# motor_controller.net
KiCad netlist of a schematic drawn in Altium Designer
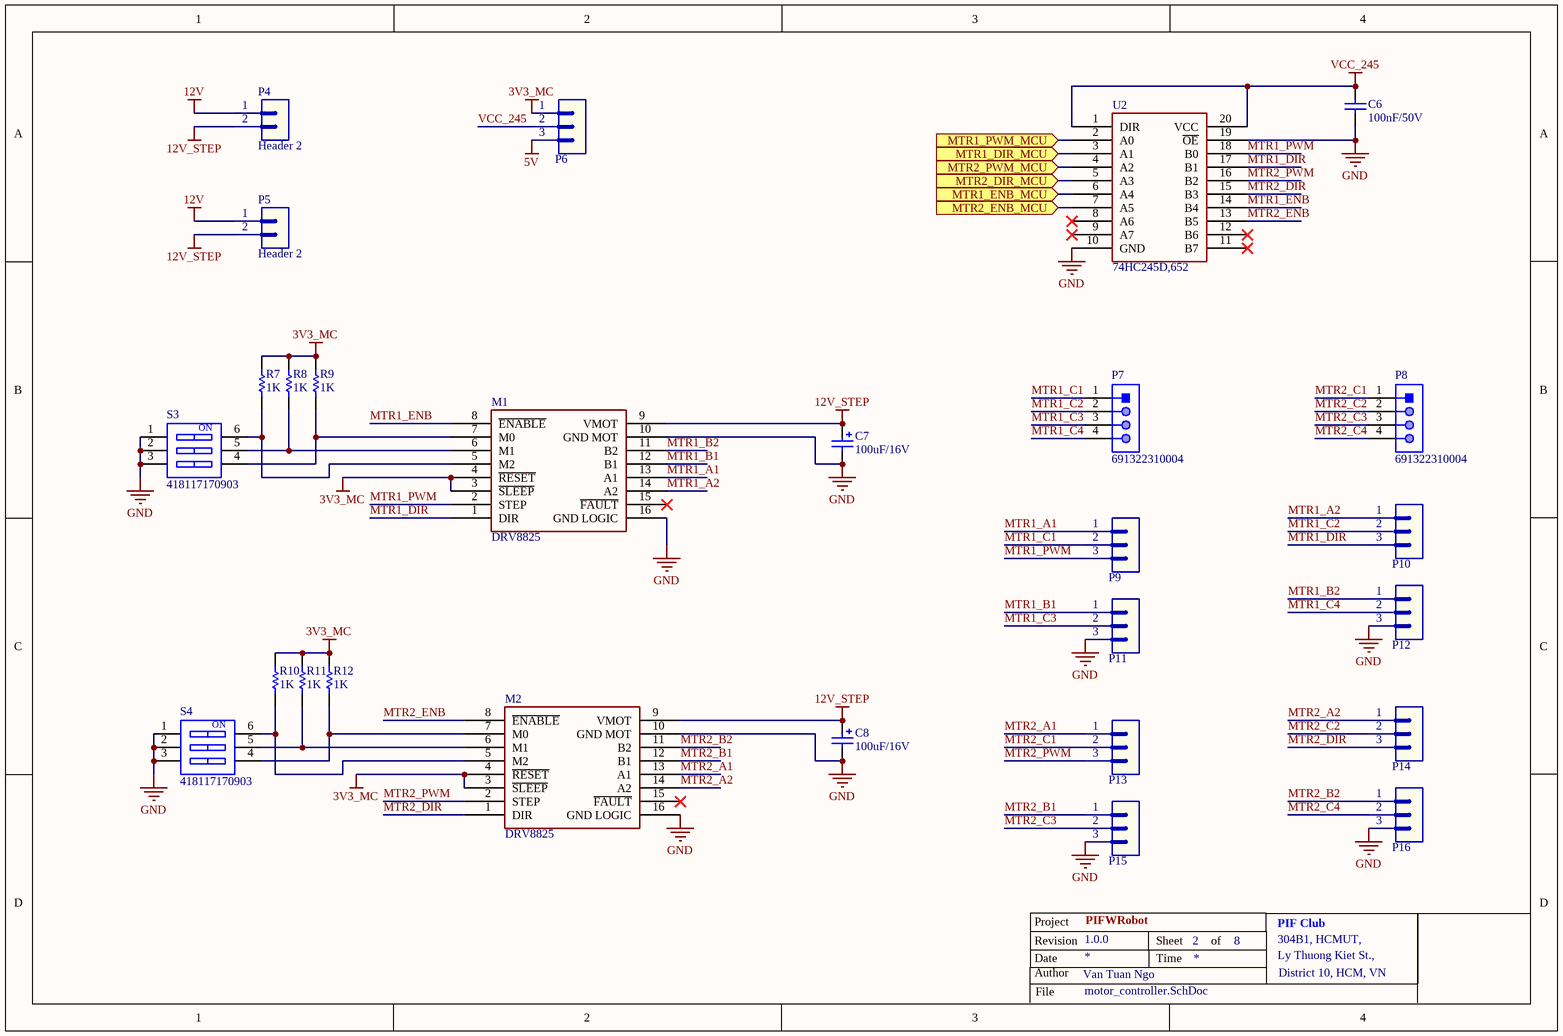
[diagram p0: motor_controller.SchDoc]

(export (version "E")
  (design (tool "Eeschema 10.0.6"))
  (components
    (comp (ref "C6")
      (value "100nF/50V")
      (footprint "CAP-SM-0805")
      (description "CAP CER 0.1UF 50V Y5V 0805")
      (fields
        (field (name "MANUFACTURER") "Samsung Electro-Mechanics")
        (field (name "MANUFACTURER PART NUMBER") "CL21F104ZBCNNNC")
      )
      (libsource (lib "Capacitor") (part "Cap-100nF-50V-0805"))
    )
    (comp (ref "C7")
      (value "100uF/16V")
      (footprint "CAP-SM-AL-SIZE-D-D6L6")
      (description "CAP ALUM 100UF 20% 16V SMD")
      (fields
        (field (name "MANUFACTURER") "Nichicon")
        (field (name "MANUFACTURER PART NUMBER") "UWX1C101MCL1GB")
      )
      (libsource (lib "Capacitor") (part "Cap-Al-100uF-16V-D6L5"))
    )
    (comp (ref "C8")
      (value "100uF/16V")
      (footprint "CAP-SM-AL-SIZE-D-D6L6")
      (description "CAP ALUM 100UF 20% 16V SMD")
      (fields
        (field (name "MANUFACTURER") "Nichicon")
        (field (name "MANUFACTURER PART NUMBER") "UWX1C101MCL1GB")
      )
      (libsource (lib "Capacitor") (part "Cap-Al-100uF-16V-D6L5"))
    )
    (comp (ref "M1") (value "DRV8825") (footprint "DRV8825") (libsource (lib "PIFWRobot") (part "DRV8825")))
    (comp (ref "M2") (value "DRV8825") (footprint "DRV8825") (libsource (lib "PIFWRobot") (part "DRV8825")))
    (comp (ref "P4")
      (value "Header 2")
      (footprint "JP2")
      (description "Header, 2-Pin")
      (fields (field (name "LOCAL SUPPLIER PART NUMBER") "x") (field (name "PUBLISHER") "Altium Limited"))
      (libsource (lib "Header-Connector") (part "Header 2"))
    )
    (comp (ref "P5")
      (value "Header 2")
      (footprint "JP2")
      (description "Header, 2-Pin")
      (fields (field (name "LOCAL SUPPLIER PART NUMBER") "x") (field (name "PUBLISHER") "Altium Limited"))
      (libsource (lib "Header-Connector") (part "Header 2"))
    )
    (comp (ref "P6")
      (value "Header 3")
      (footprint "JP3")
      (description "Header, 3-Pin")
      (fields (field (name "LOCAL SUPPLIER PART NUMBER") "x") (field (name "PUBLISHER") "Altium Limited"))
      (libsource (lib "Header-Connector") (part "Header 3"))
    )
    (comp (ref "P7")
      (value "691322310004")
      (footprint "691322310004")
      (description "WR-TBL Serie 322 Horizontal PCB Header, Pluggable, pitch 3.81mm, 4p")
      (fields (field (name "LOCAL SUPLIER PART NUMBER") "x") (field (name "PUBLISHER") "Wurth Elektronik"))
      (libsource (lib "terminal_block") (part "691322310004"))
    )
    (comp (ref "P8")
      (value "691322310004")
      (footprint "691322310004")
      (description "WR-TBL Serie 322 Horizontal PCB Header, Pluggable, pitch 3.81mm, 4p")
      (fields (field (name "LOCAL SUPLIER PART NUMBER") "x") (field (name "PUBLISHER") "Wurth Elektronik"))
      (libsource (lib "terminal_block") (part "691322310004"))
    )
    (comp (ref "P9")
      (value "Header 3")
      (footprint "JP3")
      (description "Header, 3-Pin")
      (fields (field (name "LOCAL SUPPLIER PART NUMBER") "x") (field (name "PUBLISHER") "Altium Limited"))
      (libsource (lib "Header-Connector") (part "Header 3"))
    )
    (comp (ref "P10")
      (value "Header 3")
      (footprint "JP3")
      (description "Header, 3-Pin")
      (fields (field (name "LOCAL SUPPLIER PART NUMBER") "x") (field (name "PUBLISHER") "Altium Limited"))
      (libsource (lib "Header-Connector") (part "Header 3"))
    )
    (comp (ref "P11")
      (value "Header 3")
      (footprint "JP3")
      (description "Header, 3-Pin")
      (fields (field (name "LOCAL SUPPLIER PART NUMBER") "x") (field (name "PUBLISHER") "Altium Limited"))
      (libsource (lib "Header-Connector") (part "Header 3"))
    )
    (comp (ref "P12")
      (value "Header 3")
      (footprint "JP3")
      (description "Header, 3-Pin")
      (fields (field (name "LOCAL SUPPLIER PART NUMBER") "x") (field (name "PUBLISHER") "Altium Limited"))
      (libsource (lib "Header-Connector") (part "Header 3"))
    )
    (comp (ref "P13")
      (value "Header 3")
      (footprint "JP3")
      (description "Header, 3-Pin")
      (fields (field (name "LOCAL SUPPLIER PART NUMBER") "x") (field (name "PUBLISHER") "Altium Limited"))
      (libsource (lib "Header-Connector") (part "Header 3"))
    )
    (comp (ref "P14")
      (value "Header 3")
      (footprint "JP3")
      (description "Header, 3-Pin")
      (fields (field (name "LOCAL SUPPLIER PART NUMBER") "x") (field (name "PUBLISHER") "Altium Limited"))
      (libsource (lib "Header-Connector") (part "Header 3"))
    )
    (comp (ref "P15")
      (value "Header 3")
      (footprint "JP3")
      (description "Header, 3-Pin")
      (fields (field (name "LOCAL SUPPLIER PART NUMBER") "x") (field (name "PUBLISHER") "Altium Limited"))
      (libsource (lib "Header-Connector") (part "Header 3"))
    )
    (comp (ref "P16")
      (value "Header 3")
      (footprint "JP3")
      (description "Header, 3-Pin")
      (fields (field (name "LOCAL SUPPLIER PART NUMBER") "x") (field (name "PUBLISHER") "Altium Limited"))
      (libsource (lib "Header-Connector") (part "Header 3"))
    )
    (comp (ref "R7")
      (value "1K")
      (footprint "Resistor:RES-SM-0805")
      (description "RES 1K OHM 1% 1/4W 0805")
      (fields
        (field (name "MANUFACTURER") "Stackpole Electronics Inc")
        (field (name "MANUFACTURER PART NUMBER") "RNCP0805FTD1K00")
      )
      (libsource (lib "Resistor") (part "Res-1K-0805"))
    )
    (comp (ref "R8")
      (value "1K")
      (footprint "Resistor:RES-SM-0805")
      (description "RES 1K OHM 1% 1/4W 0805")
      (fields
        (field (name "MANUFACTURER") "Stackpole Electronics Inc")
        (field (name "MANUFACTURER PART NUMBER") "RNCP0805FTD1K00")
      )
      (libsource (lib "Resistor") (part "Res-1K-0805"))
    )
    (comp (ref "R9")
      (value "1K")
      (footprint "Resistor:RES-SM-0805")
      (description "RES 1K OHM 1% 1/4W 0805")
      (fields
        (field (name "MANUFACTURER") "Stackpole Electronics Inc")
        (field (name "MANUFACTURER PART NUMBER") "RNCP0805FTD1K00")
      )
      (libsource (lib "Resistor") (part "Res-1K-0805"))
    )
    (comp (ref "R10")
      (value "1K")
      (footprint "Resistor:RES-SM-0805")
      (description "RES 1K OHM 1% 1/4W 0805")
      (fields
        (field (name "MANUFACTURER") "Stackpole Electronics Inc")
        (field (name "MANUFACTURER PART NUMBER") "RNCP0805FTD1K00")
      )
      (libsource (lib "Resistor") (part "Res-1K-0805"))
    )
    (comp (ref "R11")
      (value "1K")
      (footprint "Resistor:RES-SM-0805")
      (description "RES 1K OHM 1% 1/4W 0805")
      (fields
        (field (name "MANUFACTURER") "Stackpole Electronics Inc")
        (field (name "MANUFACTURER PART NUMBER") "RNCP0805FTD1K00")
      )
      (libsource (lib "Resistor") (part "Res-1K-0805"))
    )
    (comp (ref "R12")
      (value "1K")
      (footprint "Resistor:RES-SM-0805")
      (description "RES 1K OHM 1% 1/4W 0805")
      (fields
        (field (name "MANUFACTURER") "Stackpole Electronics Inc")
        (field (name "MANUFACTURER PART NUMBER") "RNCP0805FTD1K00")
      )
      (libsource (lib "Resistor") (part "Res-1K-0805"))
    )
    (comp (ref "S3")
      (value "418117170903")
      (footprint "418117170903")
      (description "WS-DITV Compact THT Dip Switch, Flat Actuator, pitch 2.54mm, 3p")
      (fields (field (name "LOCAL SUPPLIER PART NUMBER") "x") (field (name "PUBLISHER") "Wurth Elektronik"))
      (libsource (lib "dip_sw") (part "418117170903"))
    )
    (comp (ref "S4")
      (value "418117170903")
      (footprint "418117170903")
      (description "WS-DITV Compact THT Dip Switch, Flat Actuator, pitch 2.54mm, 3p")
      (fields (field (name "LOCAL SUPPLIER PART NUMBER") "x") (field (name "PUBLISHER") "Wurth Elektronik"))
      (libsource (lib "dip_sw") (part "418117170903"))
    )
    (comp (ref "U2")
      (value "74HC245D,652")
      (footprint "SOT163-1_NEX")
      (fields (field (name "COPYRIGHT") "Copyright (C) 2016 Accelerated Designs. All rights reserved"))
      (libsource (lib "PIFWRobot") (part "74HC245D,652"))
    )
  )
  (nets
    (net (code "1") (name "/MTR1_A1") (class "Default")
      (node (ref "M1") (pin "13") (pinfunction "A1_13") (pintype "passive"))
      (node (ref "P9") (pin "1") (pinfunction "1_1") (pintype "passive"))
    )
    (net (code "2") (name "/MTR1_A2") (class "Default")
      (node (ref "M1") (pin "14") (pinfunction "A2_14") (pintype "passive"))
      (node (ref "P10") (pin "1") (pinfunction "1_1") (pintype "passive"))
    )
    (net (code "3") (name "/MTR1_B1") (class "Default")
      (node (ref "M1") (pin "12") (pinfunction "B1_12") (pintype "passive"))
      (node (ref "P11") (pin "1") (pinfunction "1_1") (pintype "passive"))
    )
    (net (code "4") (name "/MTR1_B2") (class "Default")
      (node (ref "M1") (pin "11") (pinfunction "B2_11") (pintype "passive"))
      (node (ref "P12") (pin "1") (pinfunction "1_1") (pintype "passive"))
    )
    (net (code "5") (name "/MTR1_C1") (class "Default")
      (node (ref "P7") (pin "1") (pinfunction "1_1") (pintype "passive"))
      (node (ref "P9") (pin "2") (pinfunction "2_2") (pintype "passive"))
    )
    (net (code "6") (name "/MTR1_C2") (class "Default")
      (node (ref "P10") (pin "2") (pinfunction "2_2") (pintype "passive"))
      (node (ref "P7") (pin "2") (pinfunction "2_2") (pintype "passive"))
    )
    (net (code "7") (name "/MTR1_C3") (class "Default")
      (node (ref "P11") (pin "2") (pinfunction "2_2") (pintype "passive"))
      (node (ref "P7") (pin "3") (pinfunction "3_3") (pintype "passive"))
    )
    (net (code "8") (name "/MTR1_C4") (class "Default")
      (node (ref "P12") (pin "2") (pinfunction "2_2") (pintype "passive"))
      (node (ref "P7") (pin "4") (pinfunction "4_4") (pintype "passive"))
    )
    (net (code "9") (name "/MTR1_DIR") (class "Default")
      (node (ref "M1") (pin "1") (pinfunction "DIR_1") (pintype "passive"))
      (node (ref "P10") (pin "3") (pinfunction "3_3") (pintype "passive"))
      (node (ref "U2") (pin "17") (pinfunction "B1_17") (pintype "passive"))
    )
    (net (code "10") (name "/MTR1_DIR_MCU") (class "Default")
      (node (ref "U2") (pin "3") (pinfunction "A1_3") (pintype "passive"))
    )
    (net (code "11") (name "/MTR1_ENB") (class "Default")
      (node (ref "M1") (pin "8") (pinfunction "~{ENABLE}_8") (pintype "passive"))
      (node (ref "U2") (pin "14") (pinfunction "B4_14") (pintype "passive"))
    )
    (net (code "12") (name "/MTR1_ENB_MCU") (class "Default")
      (node (ref "U2") (pin "6") (pinfunction "A4_6") (pintype "passive"))
    )
    (net (code "13") (name "/MTR1_PWM") (class "Default")
      (node (ref "M1") (pin "2") (pinfunction "STEP_2") (pintype "passive"))
      (node (ref "P9") (pin "3") (pinfunction "3_3") (pintype "passive"))
      (node (ref "U2") (pin "18") (pinfunction "B0_18") (pintype "passive"))
    )
    (net (code "14") (name "/MTR1_PWM_MCU") (class "Default")
      (node (ref "U2") (pin "2") (pinfunction "A0_2") (pintype "passive"))
    )
    (net (code "15") (name "/MTR2_A1") (class "Default")
      (node (ref "M2") (pin "13") (pinfunction "A1_13") (pintype "passive"))
      (node (ref "P13") (pin "1") (pinfunction "1_1") (pintype "passive"))
    )
    (net (code "16") (name "/MTR2_A2") (class "Default")
      (node (ref "M2") (pin "14") (pinfunction "A2_14") (pintype "passive"))
      (node (ref "P14") (pin "1") (pinfunction "1_1") (pintype "passive"))
    )
    (net (code "17") (name "/MTR2_B1") (class "Default")
      (node (ref "M2") (pin "12") (pinfunction "B1_12") (pintype "passive"))
      (node (ref "P15") (pin "1") (pinfunction "1_1") (pintype "passive"))
    )
    (net (code "18") (name "/MTR2_B2") (class "Default")
      (node (ref "M2") (pin "11") (pinfunction "B2_11") (pintype "passive"))
      (node (ref "P16") (pin "1") (pinfunction "1_1") (pintype "passive"))
    )
    (net (code "19") (name "/MTR2_C1") (class "Default")
      (node (ref "P13") (pin "2") (pinfunction "2_2") (pintype "passive"))
      (node (ref "P8") (pin "1") (pinfunction "1_1") (pintype "passive"))
    )
    (net (code "20") (name "/MTR2_C2") (class "Default")
      (node (ref "P14") (pin "2") (pinfunction "2_2") (pintype "passive"))
      (node (ref "P8") (pin "2") (pinfunction "2_2") (pintype "passive"))
    )
    (net (code "21") (name "/MTR2_C3") (class "Default")
      (node (ref "P15") (pin "2") (pinfunction "2_2") (pintype "passive"))
      (node (ref "P8") (pin "3") (pinfunction "3_3") (pintype "passive"))
    )
    (net (code "22") (name "/MTR2_C4") (class "Default")
      (node (ref "P16") (pin "2") (pinfunction "2_2") (pintype "passive"))
      (node (ref "P8") (pin "4") (pinfunction "4_4") (pintype "passive"))
    )
    (net (code "23") (name "/MTR2_DIR") (class "Default")
      (node (ref "M2") (pin "1") (pinfunction "DIR_1") (pintype "passive"))
      (node (ref "P14") (pin "3") (pinfunction "3_3") (pintype "passive"))
      (node (ref "U2") (pin "15") (pinfunction "B3_15") (pintype "passive"))
    )
    (net (code "24") (name "/MTR2_DIR_MCU") (class "Default")
      (node (ref "U2") (pin "5") (pinfunction "A3_5") (pintype "passive"))
    )
    (net (code "25") (name "/MTR2_ENB") (class "Default")
      (node (ref "M2") (pin "8") (pinfunction "~{ENABLE}_8") (pintype "passive"))
      (node (ref "U2") (pin "13") (pinfunction "B5_13") (pintype "passive"))
    )
    (net (code "26") (name "/MTR2_ENB_MCU") (class "Default")
      (node (ref "U2") (pin "7") (pinfunction "A5_7") (pintype "passive"))
    )
    (net (code "27") (name "/MTR2_PWM") (class "Default")
      (node (ref "M2") (pin "2") (pinfunction "STEP_2") (pintype "passive"))
      (node (ref "P13") (pin "3") (pinfunction "3_3") (pintype "passive"))
      (node (ref "U2") (pin "16") (pinfunction "B2_16") (pintype "passive"))
    )
    (net (code "28") (name "/MTR2_PWM_MCU") (class "Default")
      (node (ref "U2") (pin "4") (pinfunction "A2_4") (pintype "passive"))
    )
    (net (code "29") (name "3V3_MC") (class "Default")
      (node (ref "M1") (pin "3") (pinfunction "~{SLEEP}_3") (pintype "passive"))
      (node (ref "M1") (pin "4") (pinfunction "~{RESET}_4") (pintype "passive"))
      (node (ref "M2") (pin "3") (pinfunction "~{SLEEP}_3") (pintype "passive"))
      (node (ref "M2") (pin "4") (pinfunction "~{RESET}_4") (pintype "passive"))
      (node (ref "P6") (pin "1") (pinfunction "1_1") (pintype "passive"))
      (node (ref "R10") (pin "2") (pinfunction "2_2") (pintype "passive"))
      (node (ref "R11") (pin "2") (pinfunction "2_2") (pintype "passive"))
      (node (ref "R12") (pin "2") (pinfunction "2_2") (pintype "passive"))
      (node (ref "R7") (pin "2") (pinfunction "2_2") (pintype "passive"))
      (node (ref "R8") (pin "2") (pinfunction "2_2") (pintype "passive"))
      (node (ref "R9") (pin "2") (pinfunction "2_2") (pintype "passive"))
    )
    (net (code "30") (name "5V") (class "Default")
      (node (ref "P6") (pin "3") (pinfunction "3_3") (pintype "passive"))
    )
    (net (code "31") (name "12V") (class "Default")
      (node (ref "P4") (pin "1") (pinfunction "1_1") (pintype "passive"))
      (node (ref "P5") (pin "1") (pinfunction "1_1") (pintype "passive"))
    )
    (net (code "32") (name "12V_STEP") (class "Default")
      (node (ref "C7") (pin "1") (pinfunction "1_1") (pintype "passive"))
      (node (ref "C8") (pin "1") (pinfunction "1_1") (pintype "passive"))
      (node (ref "M1") (pin "9") (pinfunction "VMOT_9") (pintype "passive"))
      (node (ref "M2") (pin "9") (pinfunction "VMOT_9") (pintype "passive"))
      (node (ref "P4") (pin "2") (pinfunction "2_2") (pintype "passive"))
      (node (ref "P5") (pin "2") (pinfunction "2_2") (pintype "passive"))
    )
    (net (code "33") (name "GND") (class "Default")
      (node (ref "C6") (pin "1") (pinfunction "1_1") (pintype "passive"))
      (node (ref "C7") (pin "2") (pinfunction "2_2") (pintype "passive"))
      (node (ref "C8") (pin "2") (pinfunction "2_2") (pintype "passive"))
      (node (ref "M1") (pin "10") (pinfunction "GND_MOT_10") (pintype "passive"))
      (node (ref "M1") (pin "16") (pinfunction "GND_LOGIC_16") (pintype "passive"))
      (node (ref "M2") (pin "10") (pinfunction "GND_MOT_10") (pintype "passive"))
      (node (ref "M2") (pin "16") (pinfunction "GND_LOGIC_16") (pintype "passive"))
      (node (ref "P11") (pin "3") (pinfunction "3_3") (pintype "passive"))
      (node (ref "P12") (pin "3") (pinfunction "3_3") (pintype "passive"))
      (node (ref "P15") (pin "3") (pinfunction "3_3") (pintype "passive"))
      (node (ref "P16") (pin "3") (pinfunction "3_3") (pintype "passive"))
      (node (ref "S3") (pin "1") (pinfunction "1_1") (pintype "passive"))
      (node (ref "S3") (pin "2") (pinfunction "2_2") (pintype "passive"))
      (node (ref "S3") (pin "3") (pinfunction "3_3") (pintype "passive"))
      (node (ref "S4") (pin "1") (pinfunction "1_1") (pintype "passive"))
      (node (ref "S4") (pin "2") (pinfunction "2_2") (pintype "passive"))
      (node (ref "S4") (pin "3") (pinfunction "3_3") (pintype "passive"))
      (node (ref "U2") (pin "10") (pinfunction "GND_10") (pintype "passive"))
      (node (ref "U2") (pin "19") (pinfunction "~{OE}_19") (pintype "passive"))
    )
    (net (code "34") (name "Net-(M1-M0)") (class "Default")
      (node (ref "M1") (pin "7") (pinfunction "M0_7") (pintype "passive"))
      (node (ref "R9") (pin "1") (pinfunction "1_1") (pintype "passive"))
      (node (ref "S3") (pin "4") (pinfunction "4_4") (pintype "passive"))
    )
    (net (code "35") (name "Net-(M1-M1)") (class "Default")
      (node (ref "M1") (pin "6") (pinfunction "M1_6") (pintype "passive"))
      (node (ref "R8") (pin "1") (pinfunction "1_1") (pintype "passive"))
      (node (ref "S3") (pin "5") (pinfunction "5_5") (pintype "passive"))
    )
    (net (code "36") (name "Net-(M1-M2)") (class "Default")
      (node (ref "M1") (pin "5") (pinfunction "M2_5") (pintype "passive"))
      (node (ref "R7") (pin "1") (pinfunction "1_1") (pintype "passive"))
      (node (ref "S3") (pin "6") (pinfunction "6_6") (pintype "passive"))
    )
    (net (code "37") (name "Net-(M2-M0)") (class "Default")
      (node (ref "M2") (pin "7") (pinfunction "M0_7") (pintype "passive"))
      (node (ref "R12") (pin "1") (pinfunction "1_1") (pintype "passive"))
      (node (ref "S4") (pin "4") (pinfunction "4_4") (pintype "passive"))
    )
    (net (code "38") (name "Net-(M2-M1)") (class "Default")
      (node (ref "M2") (pin "6") (pinfunction "M1_6") (pintype "passive"))
      (node (ref "R11") (pin "1") (pinfunction "1_1") (pintype "passive"))
      (node (ref "S4") (pin "5") (pinfunction "5_5") (pintype "passive"))
    )
    (net (code "39") (name "Net-(M2-M2)") (class "Default")
      (node (ref "M2") (pin "5") (pinfunction "M2_5") (pintype "passive"))
      (node (ref "R10") (pin "1") (pinfunction "1_1") (pintype "passive"))
      (node (ref "S4") (pin "6") (pinfunction "6_6") (pintype "passive"))
    )
    (net (code "40") (name "VCC_245") (class "Default")
      (node (ref "C6") (pin "2") (pinfunction "2_2") (pintype "passive"))
      (node (ref "P6") (pin "2") (pinfunction "2_2") (pintype "passive"))
      (node (ref "U2") (pin "1") (pinfunction "DIR_1") (pintype "passive"))
      (node (ref "U2") (pin "20") (pinfunction "VCC_20") (pintype "passive"))
    )
    (net (code "41") (name "unconnected-(M1-~{FAULT}-Pad15)") (class "Default")
      (node (ref "M1") (pin "15") (pinfunction "~{FAULT}_15") (pintype "passive+no_connect"))
    )
    (net (code "42") (name "unconnected-(M2-~{FAULT}-Pad15)") (class "Default")
      (node (ref "M2") (pin "15") (pinfunction "~{FAULT}_15") (pintype "passive+no_connect"))
    )
    (net (code "43") (name "unconnected-(U2-A6-Pad8)") (class "Default")
      (node (ref "U2") (pin "8") (pinfunction "A6_8") (pintype "passive+no_connect"))
    )
    (net (code "44") (name "unconnected-(U2-A7-Pad9)") (class "Default")
      (node (ref "U2") (pin "9") (pinfunction "A7_9") (pintype "passive+no_connect"))
    )
    (net (code "45") (name "unconnected-(U2-B6-Pad12)") (class "Default")
      (node (ref "U2") (pin "12") (pinfunction "B6_12") (pintype "passive+no_connect"))
    )
    (net (code "46") (name "unconnected-(U2-B7-Pad11)") (class "Default")
      (node (ref "U2") (pin "11") (pinfunction "B7_11") (pintype "passive+no_connect"))
    )
  )
)
